# STB_PeltierDriver.net
KiCad netlist of a schematic drawn in Altium Designer
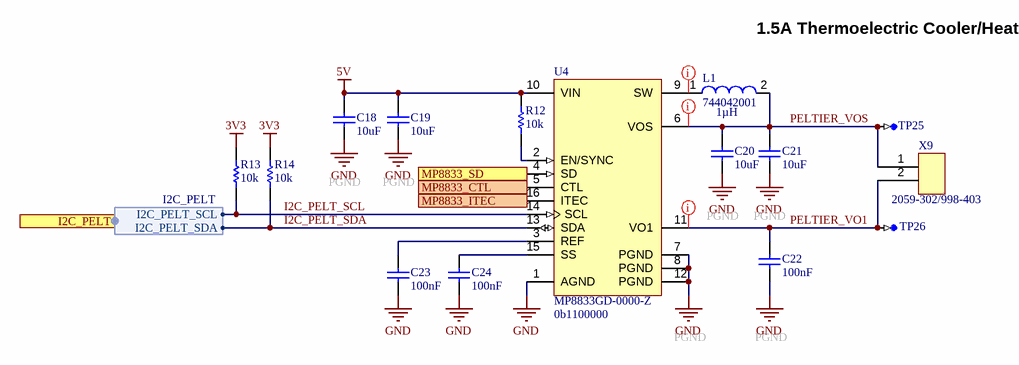
[diagram p0: STB_PeltierDriver.SchDoc]

(export (version "E")
  (design (tool "Eeschema 10.0.6"))
  (components
    (comp (ref "C18")
      (value "10uF")
      (footprint "CAPC0603(1608)100_L")
      (description "CAP 10uF 10V ±10% 0603 (1608 Metric) Thickness 1mm SMD")
      (fields (field (name "TOLERANCE") "Â±10%") (field (name "MANUFACTURER") "Samsung"))
      (libsource (lib "Altium Content Vault") (part "CMP-1035-02799-1"))
    )
    (comp (ref "C19")
      (value "10uF")
      (footprint "CAPC0603(1608)100_L")
      (description "CAP 10uF 10V ±10% 0603 (1608 Metric) Thickness 1mm SMD")
      (fields (field (name "TOLERANCE") "Â±10%") (field (name "MANUFACTURER") "Samsung"))
      (libsource (lib "Altium Content Vault") (part "CMP-1035-02799-1"))
    )
    (comp (ref "C20")
      (value "10uF")
      (footprint "CAPC0603(1608)100_L")
      (description "CAP 10uF 10V ±10% 0603 (1608 Metric) Thickness 1mm SMD")
      (fields (field (name "TOLERANCE") "Â±10%") (field (name "MANUFACTURER") "Samsung"))
      (libsource (lib "Altium Content Vault") (part "CMP-1035-02799-1"))
    )
    (comp (ref "C21")
      (value "10uF")
      (footprint "CAPC0603(1608)100_L")
      (description "CAP 10uF 10V ±10% 0603 (1608 Metric) Thickness 1mm SMD")
      (fields (field (name "TOLERANCE") "Â±10%") (field (name "MANUFACTURER") "Samsung"))
      (libsource (lib "Altium Content Vault") (part "CMP-1035-02799-1"))
    )
    (comp (ref "C22")
      (value "100nF")
      (footprint "CAPC1050X55X23LL05T13")
      (description "Chip Capacitor, 100 nF, +/- 10%, 16 V, -55 to 125 degC, 0402 (1005 Metric), RoHS, Tape and Reel")
      (fields
        (field (name "MANUFACTURER") "Samsung Electro-Mechanics")
        (field (name "MANUFACTURER PART NUMBER") "CL05B104KO5NNNC")
      )
      (libsource (lib "Altium Content Vault") (part "CAP-NP-2"))
    )
    (comp (ref "C23")
      (value "100nF")
      (footprint "CAPC1050X55X23LL05T13")
      (description "Chip Capacitor, 100 nF, +/- 10%, 16 V, -55 to 125 degC, 0402 (1005 Metric), RoHS, Tape and Reel")
      (fields
        (field (name "MANUFACTURER") "Samsung Electro-Mechanics")
        (field (name "MANUFACTURER PART NUMBER") "CL05B104KO5NNNC")
      )
      (libsource (lib "Altium Content Vault") (part "CAP-NP-2"))
    )
    (comp (ref "C24")
      (value "100nF")
      (footprint "CAPC1050X55X23LL05T13")
      (description "Chip Capacitor, 100 nF, +/- 10%, 16 V, -55 to 125 degC, 0402 (1005 Metric), RoHS, Tape and Reel")
      (fields
        (field (name "MANUFACTURER") "Samsung Electro-Mechanics")
        (field (name "MANUFACTURER PART NUMBER") "CL05B104KO5NNNC")
      )
      (libsource (lib "Altium Content Vault") (part "CAP-NP-2"))
    )
    (comp (ref "L1")
      (value "744042001")
      (footprint "WE-TPC-4818-M")
      (description "SMD Shielded Tiny Power Inductor WE-TPC, L = 1.00 µH")
      (fields (field (name "MANUFACTURER") "Wurth Electronics") (field (name "TOLERANCE") "30%"))
      (libsource (lib "Altium Content Vault") (part "PAS-IND-INDUCTOR-2"))
    )
    (comp (ref "R12")
      (value "10k")
      (footprint "RESC1005X40X25LL05T05")
      (description "Chip Resistor, 10 KOhm, +/- 1%, 0.1 W, -55 to 155 degC, 0402 (1005 Metric), RoHS, Tape and Reel")
      (fields (field (name "TOLERANCE") "1%") (field (name "MANUFACTURER") "Panasonic"))
      (libsource (lib "Altium Content Vault") (part "RES-2"))
    )
    (comp (ref "R13")
      (value "10k")
      (footprint "RESC1005X40X25LL05T05")
      (description "Chip Resistor, 10 KOhm, +/- 1%, 0.1 W, -55 to 155 degC, 0402 (1005 Metric), RoHS, Tape and Reel")
      (fields (field (name "TOLERANCE") "1%") (field (name "MANUFACTURER") "Panasonic"))
      (libsource (lib "Altium Content Vault") (part "RES-2"))
    )
    (comp (ref "R14")
      (value "10k")
      (footprint "RESC1005X40X25LL05T05")
      (description "Chip Resistor, 10 KOhm, +/- 1%, 0.1 W, -55 to 155 degC, 0402 (1005 Metric), RoHS, Tape and Reel")
      (fields (field (name "TOLERANCE") "1%") (field (name "MANUFACTURER") "Panasonic"))
      (libsource (lib "Altium Content Vault") (part "RES-2"))
    )
    (comp (ref "TP25")
      (value "testPoint_1mm")
      (footprint "TP-SM-C-100")
      (description "testPoint 1mm")
      (libsource (lib "STB_Schlib") (part "testPoint_1mm"))
    )
    (comp (ref "TP26")
      (value "testPoint_1mm")
      (footprint "TP-SM-C-100")
      (description "testPoint 1mm")
      (libsource (lib "STB_Schlib") (part "testPoint_1mm"))
    )
    (comp (ref "U4")
      (value "MP8833GD-0000-Z")
      (footprint "QFN40P200X300X100-16N")
      (description "1.5A THERMOELECTRIC COOLER CONTR")
      (fields
        (field (name "MFR") "Monolithic Power Systems Inc.")
        (field (name "MANUFACTURER") "Monolithic Power Systems")
      )
      (libsource (lib "ETHZ Vault") (part "MP8833GD-0000-Z"))
    )
    (comp (ref "X9")
      (value "2059-302/998-403")
      (footprint "2059-302/998-403")
      (description "Barrier Strip Terminal Block, 3A, 0.34mm2, 1 Row(s), 1 Deck(s)")
      (fields (field (name "MANUFACTURER") "WAGO") (field (name "SAFETY APPROVAL") "UL"))
      (libsource (lib "STB_Schlib") (part "2059-302/998-403"))
    )
  )
  (nets
    (net (code "2") (name "/I2C_PELT_SCL") (class "Default")
      (node (ref "R13") (pin "1") (pinfunction "1_1") (pintype "passive"))
      (node (ref "U4") (pin "14") (pinfunction "SCL_14") (pintype "input"))
    )
    (net (code "3") (name "/I2C_PELT_SDA") (class "Default")
      (node (ref "R14") (pin "1") (pinfunction "1_1") (pintype "passive"))
      (node (ref "U4") (pin "13") (pinfunction "SDA_13") (pintype "bidirectional"))
    )
    (net (code "4") (name "/MP8833_CTL") (class "Default")
      (node (ref "U4") (pin "5") (pinfunction "CTL_5") (pintype "passive"))
    )
    (net (code "5") (name "/MP8833_ITEC") (class "Default")
      (node (ref "U4") (pin "16") (pinfunction "ITEC_16") (pintype "passive"))
    )
    (net (code "6") (name "/MP8833_SD") (class "Default")
      (node (ref "U4") (pin "4") (pinfunction "SD_4") (pintype "input"))
    )
    (net (code "7") (name "/PELTIER_VO1") (class "Default")
      (node (ref "C22") (pin "2") (pinfunction "2_2") (pintype "passive"))
      (node (ref "TP26") (pin "TP") (pinfunction "TP_TP") (pintype "input"))
      (node (ref "U4") (pin "11") (pinfunction "VO1_11") (pintype "passive"))
      (node (ref "X9") (pin "2") (pintype "passive"))
    )
    (net (code "8") (name "/PELTIER_VOS") (class "Default")
      (node (ref "C20") (pin "2") (pinfunction "2_2") (pintype "passive"))
      (node (ref "C21") (pin "2") (pinfunction "2_2") (pintype "passive"))
      (node (ref "L1") (pin "2") (pinfunction "2_2") (pintype "passive"))
      (node (ref "TP25") (pin "TP") (pinfunction "TP_TP") (pintype "input"))
      (node (ref "U4") (pin "6") (pinfunction "VOS_6") (pintype "passive"))
      (node (ref "X9") (pin "1") (pintype "passive"))
    )
    (net (code "10") (name "3V3") (class "Default")
      (node (ref "R13") (pin "2") (pinfunction "2_2") (pintype "passive"))
      (node (ref "R14") (pin "2") (pinfunction "2_2") (pintype "passive"))
    )
    (net (code "11") (name "5V") (class "Default")
      (node (ref "C18") (pin "2") (pinfunction "2_2") (pintype "passive"))
      (node (ref "C19") (pin "2") (pinfunction "2_2") (pintype "passive"))
      (node (ref "R12") (pin "2") (pinfunction "2_2") (pintype "passive"))
      (node (ref "U4") (pin "10") (pinfunction "VIN_10") (pintype "power_in"))
    )
    (net (code "12") (name "GND") (class "Default")
      (node (ref "C18") (pin "1") (pinfunction "1_1") (pintype "passive"))
      (node (ref "C19") (pin "1") (pinfunction "1_1") (pintype "passive"))
      (node (ref "C20") (pin "1") (pinfunction "1_1") (pintype "passive"))
      (node (ref "C21") (pin "1") (pinfunction "1_1") (pintype "passive"))
      (node (ref "C22") (pin "1") (pinfunction "1_1") (pintype "passive"))
      (node (ref "C23") (pin "1") (pinfunction "1_1") (pintype "passive"))
      (node (ref "C24") (pin "1") (pinfunction "1_1") (pintype "passive"))
      (node (ref "U4") (pin "1") (pinfunction "AGND_1") (pintype "power_in"))
      (node (ref "U4") (pin "12") (pinfunction "PGND_12") (pintype "power_in"))
      (node (ref "U4") (pin "7") (pinfunction "PGND_7") (pintype "power_in"))
      (node (ref "U4") (pin "8") (pinfunction "PGND_8") (pintype "power_in"))
    )
    (net (code "13") (name "Net-(U4-EN{slash}SYNC)") (class "Default")
      (node (ref "R12") (pin "1") (pinfunction "1_1") (pintype "passive"))
      (node (ref "U4") (pin "2") (pinfunction "EN/SYNC_2") (pintype "input"))
    )
    (net (code "14") (name "Net-(U4-REF)") (class "Default")
      (node (ref "C23") (pin "2") (pinfunction "2_2") (pintype "passive"))
      (node (ref "U4") (pin "3") (pinfunction "REF_3") (pintype "power_in"))
    )
    (net (code "15") (name "Net-(U4-SS)") (class "Default")
      (node (ref "C24") (pin "2") (pinfunction "2_2") (pintype "passive"))
      (node (ref "U4") (pin "15") (pinfunction "SS_15") (pintype "passive"))
    )
    (net (code "16") (name "Net-(U4-SW)") (class "Default")
      (node (ref "L1") (pin "1") (pinfunction "1_1") (pintype "passive"))
      (node (ref "U4") (pin "9") (pinfunction "SW_9") (pintype "power_in"))
    )
  )
)
